# CrackberryPi_1_0_6_2_random3.net
KiCad netlist of a schematic drawn in EAGLE
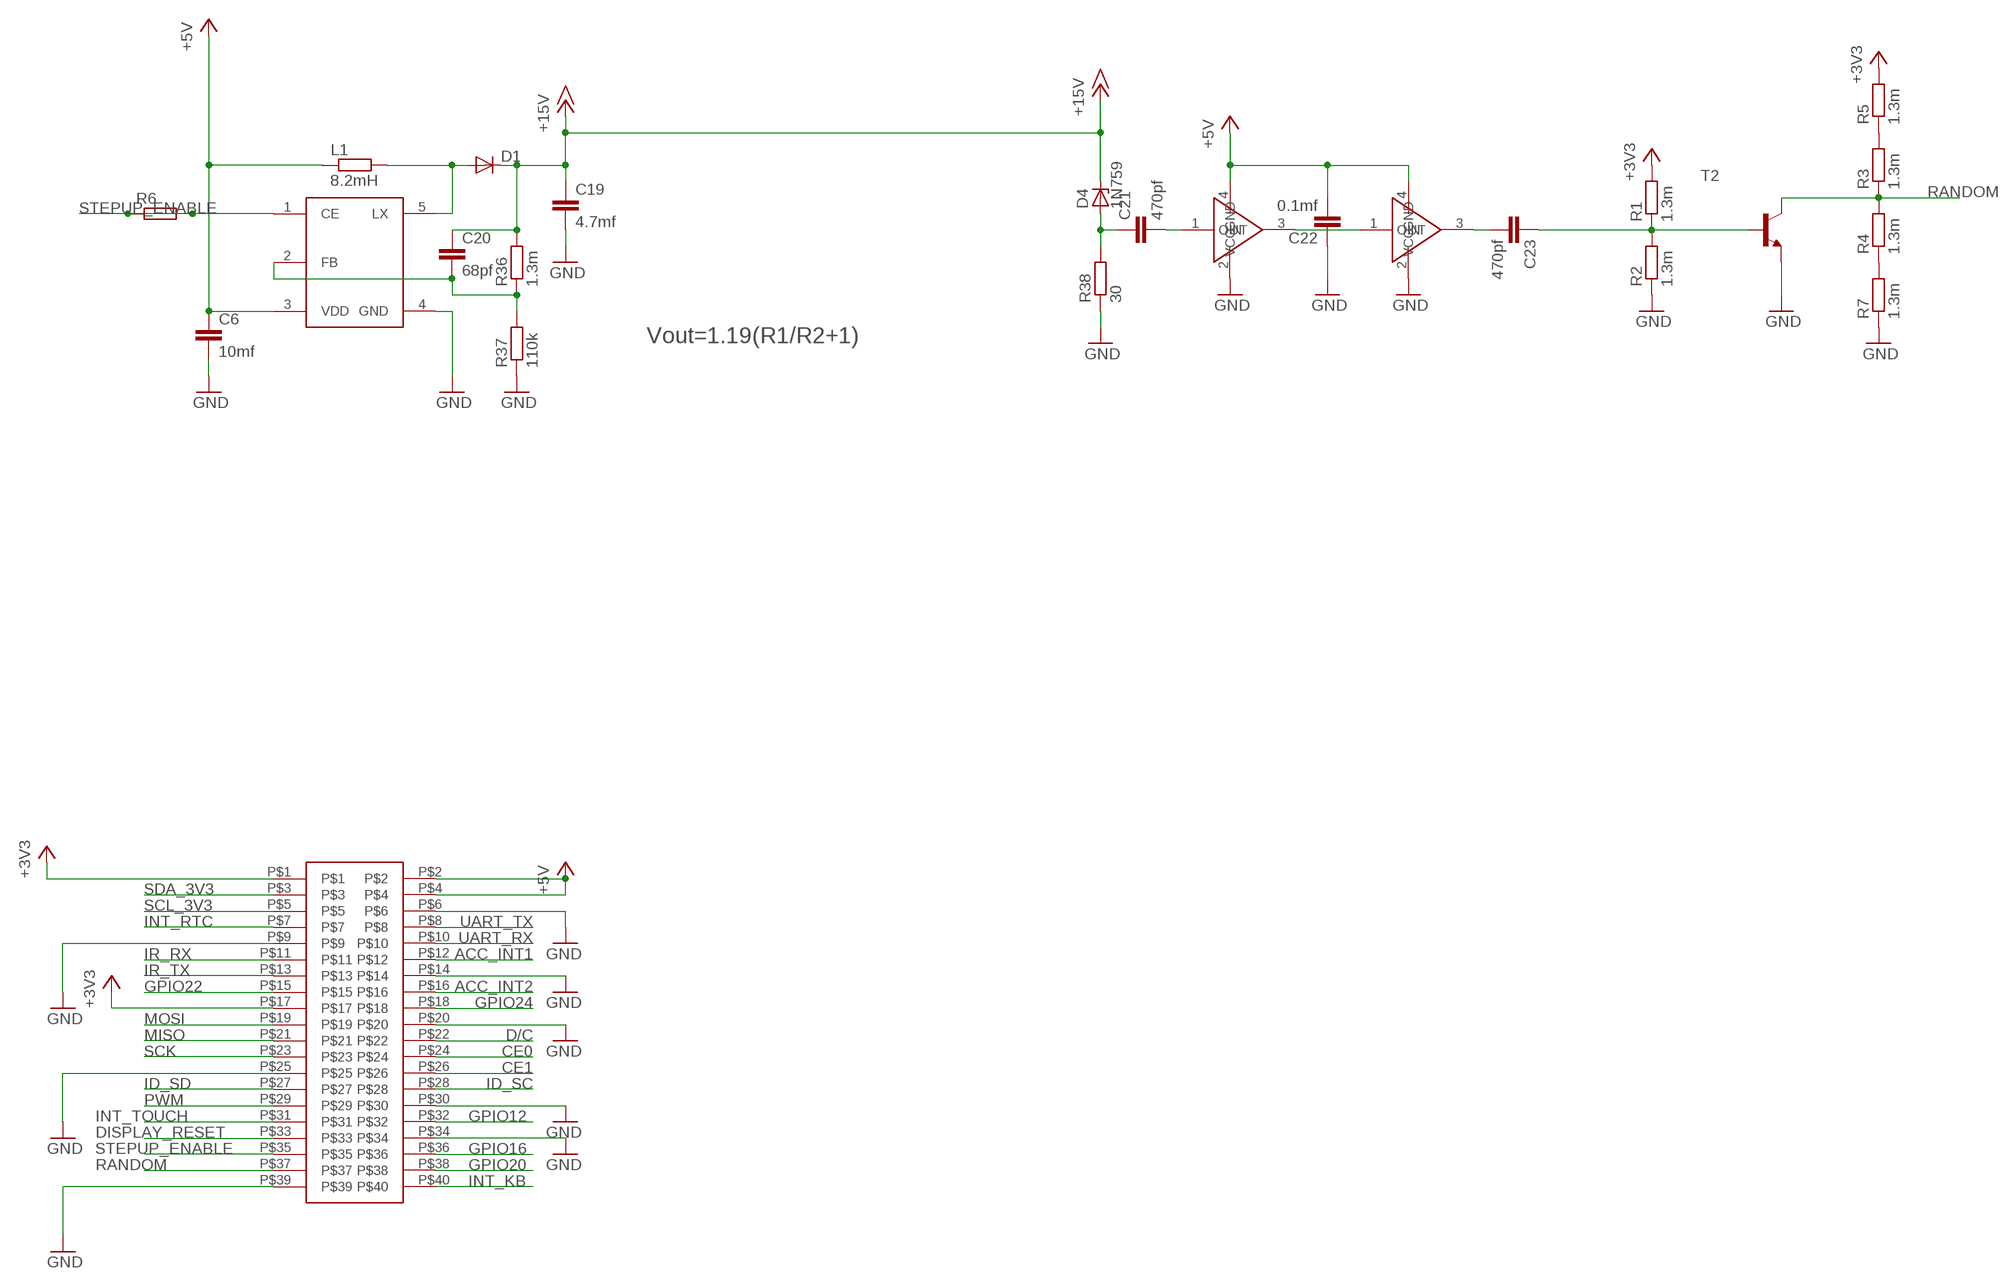
[diagram p0: schematic, sheet 1]

(export (version "E")
  (design (tool "Eeschema 10.0.6"))
  (components
    (comp (ref "C6")
      (value "10mf")
      (footprint "eagle-import:C0603")
      (libsource (lib "eagle-import") (part "C-EUC0603"))
    )
    (comp (ref "C19")
      (value "4.7mf")
      (footprint "eagle-import:C0603")
      (libsource (lib "eagle-import") (part "C-EUC0603"))
    )
    (comp (ref "C20")
      (value "68pf")
      (footprint "eagle-import:C0603")
      (libsource (lib "eagle-import") (part "C-EUC0603"))
    )
    (comp (ref "C21")
      (value "470pf")
      (footprint "eagle-import:C0603")
      (libsource (lib "eagle-import") (part "C-EUC0603"))
    )
    (comp (ref "C22")
      (value "0.1mf")
      (footprint "eagle-import:C0603")
      (libsource (lib "eagle-import") (part "C-EUC0603"))
    )
    (comp (ref "C23")
      (value "470pf")
      (footprint "eagle-import:C0603")
      (libsource (lib "eagle-import") (part "C-EUC0603"))
    )
    (comp (ref "D1")
      (value "DIODE-SOD123")
      (footprint "eagle-import:SOD123")
      (libsource (lib "eagle-import") (part "DIODE-SOD123"))
    )
    (comp (ref "D4")
      (value "1N759")
      (footprint "eagle-import:SOD80C")
      (libsource (lib "eagle-import") (part "ZENER-DIODESOD80C"))
    )
    (comp (ref "L1")
      (value "8.2mH")
      (footprint "eagle-import:R1210")
      (libsource (lib "eagle-import") (part "R-EU_R1210"))
    )
    (comp (ref "R1")
      (value "1.3m")
      (footprint "eagle-import:R0603")
      (libsource (lib "eagle-import") (part "R-EU_R0603"))
    )
    (comp (ref "R2")
      (value "1.3m")
      (footprint "eagle-import:R0603")
      (libsource (lib "eagle-import") (part "R-EU_R0603"))
    )
    (comp (ref "R3")
      (value "1.3m")
      (footprint "eagle-import:R0603")
      (libsource (lib "eagle-import") (part "R-EU_R0603"))
    )
    (comp (ref "R4")
      (value "1.3m")
      (footprint "eagle-import:R0603")
      (libsource (lib "eagle-import") (part "R-EU_R0603"))
    )
    (comp (ref "R5")
      (value "1.3m")
      (footprint "eagle-import:R0603")
      (libsource (lib "eagle-import") (part "R-EU_R0603"))
    )
    (comp (ref "R6")
      (value "R-EU_R1210")
      (footprint "eagle-import:R1210")
      (libsource (lib "eagle-import") (part "R-EU_R1210"))
    )
    (comp (ref "R7")
      (value "1.3m")
      (footprint "eagle-import:R0603")
      (libsource (lib "eagle-import") (part "R-EU_R0603"))
    )
    (comp (ref "R36")
      (value "1.3m")
      (footprint "eagle-import:R0603")
      (libsource (lib "eagle-import") (part "R-EU_R0603"))
    )
    (comp (ref "R37")
      (value "110k")
      (footprint "eagle-import:R0603")
      (libsource (lib "eagle-import") (part "R-EU_R0603"))
    )
    (comp (ref "R38")
      (value "30")
      (footprint "eagle-import:R0603")
      (libsource (lib "eagle-import") (part "R-EU_R0603"))
    )
    (comp (ref "T2")
      (value "-NPN-SOT23-EBC")
      (footprint "eagle-import:SOT23-EBC")
      (libsource (lib "eagle-import") (part "-NPN-SOT23-EBC"))
    )
    (comp (ref "U$2")
      (value "NCP1406")
      (footprint "eagle-import:SOT23-5L")
      (libsource (lib "eagle-import") (part "NCP1406"))
    )
    (comp (ref "U$3")
      (value "MAX2650")
      (footprint "eagle-import:SOT143-W")
      (libsource (lib "eagle-import") (part "MAX2650"))
    )
    (comp (ref "U$10")
      (value "MAX2650")
      (footprint "eagle-import:SOT143-W")
      (libsource (lib "eagle-import") (part "MAX2650"))
    )
    (comp (ref "U$11")
      (value "HEADER")
      (footprint "eagle-import:20X2")
      (libsource (lib "eagle-import") (part "HEADER"))
    )
  )
  (nets
    (net (code "1") (name "+3V3") (class "Default")
      (node (ref "R1") (pin "2") (pinfunction "2_2") (pintype "passive"))
      (node (ref "R5") (pin "2") (pinfunction "2_2") (pintype "passive"))
      (node (ref "U$11") (pin "P$1") (pinfunction "P$1_P$1") (pintype "bidirectional"))
      (node (ref "U$11") (pin "P$17") (pinfunction "P$17_P$17") (pintype "bidirectional"))
    )
    (net (code "2") (name "+5V") (class "Default")
      (node (ref "C22") (pin "2") (pinfunction "2_2") (pintype "passive"))
      (node (ref "C6") (pin "1") (pinfunction "1_1") (pintype "passive"))
      (node (ref "L1") (pin "1") (pinfunction "1_1") (pintype "passive"))
      (node (ref "U$10") (pin "4") (pinfunction "VCC_4") (pintype "bidirectional"))
      (node (ref "U$11") (pin "P$2") (pinfunction "P$2_P$2") (pintype "bidirectional"))
      (node (ref "U$11") (pin "P$4") (pinfunction "P$4_P$4") (pintype "bidirectional"))
      (node (ref "U$2") (pin "3") (pinfunction "VDD_3") (pintype "bidirectional"))
      (node (ref "U$3") (pin "4") (pinfunction "VCC_4") (pintype "bidirectional"))
    )
    (net (code "3") (name "+15V") (class "Default")
      (node (ref "C19") (pin "1") (pinfunction "1_1") (pintype "passive"))
      (node (ref "C20") (pin "1") (pinfunction "1_1") (pintype "passive"))
      (node (ref "D1") (pin "C") (pinfunction "C_C") (pintype "passive"))
      (node (ref "D4") (pin "C") (pinfunction "C_C") (pintype "passive"))
      (node (ref "R36") (pin "2") (pinfunction "2_2") (pintype "passive"))
    )
    (net (code "4") (name "/ACC_INT1") (class "Default")
      (node (ref "U$11") (pin "P$12") (pinfunction "P$12_P$12") (pintype "bidirectional"))
    )
    (net (code "5") (name "/ACC_INT2") (class "Default")
      (node (ref "U$11") (pin "P$16") (pinfunction "P$16_P$16") (pintype "bidirectional"))
    )
    (net (code "6") (name "/CE0") (class "Default")
      (node (ref "U$11") (pin "P$24") (pinfunction "P$24_P$24") (pintype "bidirectional"))
    )
    (net (code "7") (name "/CE1") (class "Default")
      (node (ref "U$11") (pin "P$26") (pinfunction "P$26_P$26") (pintype "bidirectional"))
    )
    (net (code "8") (name "/DISPLAY_RESET") (class "Default")
      (node (ref "U$11") (pin "P$33") (pinfunction "P$33_P$33") (pintype "bidirectional"))
    )
    (net (code "9") (name "/D{slash}C") (class "Default")
      (node (ref "U$11") (pin "P$22") (pinfunction "P$22_P$22") (pintype "bidirectional"))
    )
    (net (code "10") (name "/GPIO12") (class "Default")
      (node (ref "U$11") (pin "P$32") (pinfunction "P$32_P$32") (pintype "bidirectional"))
    )
    (net (code "11") (name "/GPIO16") (class "Default")
      (node (ref "U$11") (pin "P$36") (pinfunction "P$36_P$36") (pintype "bidirectional"))
    )
    (net (code "12") (name "/GPIO20") (class "Default")
      (node (ref "U$11") (pin "P$38") (pinfunction "P$38_P$38") (pintype "bidirectional"))
    )
    (net (code "13") (name "/GPIO22") (class "Default")
      (node (ref "U$11") (pin "P$15") (pinfunction "P$15_P$15") (pintype "bidirectional"))
    )
    (net (code "14") (name "/GPIO24") (class "Default")
      (node (ref "U$11") (pin "P$18") (pinfunction "P$18_P$18") (pintype "bidirectional"))
    )
    (net (code "15") (name "/ID_SC") (class "Default")
      (node (ref "U$11") (pin "P$28") (pinfunction "P$28_P$28") (pintype "bidirectional"))
    )
    (net (code "16") (name "/ID_SD") (class "Default")
      (node (ref "U$11") (pin "P$27") (pinfunction "P$27_P$27") (pintype "bidirectional"))
    )
    (net (code "17") (name "/INT_KB") (class "Default")
      (node (ref "U$11") (pin "P$40") (pinfunction "P$40_P$40") (pintype "bidirectional"))
    )
    (net (code "18") (name "/INT_RTC") (class "Default")
      (node (ref "U$11") (pin "P$7") (pinfunction "P$7_P$7") (pintype "bidirectional"))
    )
    (net (code "19") (name "/INT_TOUCH") (class "Default")
      (node (ref "U$11") (pin "P$31") (pinfunction "P$31_P$31") (pintype "bidirectional"))
    )
    (net (code "20") (name "/IR_RX") (class "Default")
      (node (ref "U$11") (pin "P$11") (pinfunction "P$11_P$11") (pintype "bidirectional"))
    )
    (net (code "21") (name "/IR_TX") (class "Default")
      (node (ref "U$11") (pin "P$13") (pinfunction "P$13_P$13") (pintype "bidirectional"))
    )
    (net (code "22") (name "/MISO") (class "Default")
      (node (ref "U$11") (pin "P$21") (pinfunction "P$21_P$21") (pintype "bidirectional"))
    )
    (net (code "23") (name "/MOSI") (class "Default")
      (node (ref "U$11") (pin "P$19") (pinfunction "P$19_P$19") (pintype "bidirectional"))
    )
    (net (code "24") (name "/PWM") (class "Default")
      (node (ref "U$11") (pin "P$29") (pinfunction "P$29_P$29") (pintype "bidirectional"))
    )
    (net (code "25") (name "/RANDOM") (class "Default")
      (node (ref "R3") (pin "1") (pinfunction "1_1") (pintype "passive"))
      (node (ref "R4") (pin "2") (pinfunction "2_2") (pintype "passive"))
      (node (ref "T2") (pin "C") (pinfunction "C_C") (pintype "passive"))
      (node (ref "U$11") (pin "P$37") (pinfunction "P$37_P$37") (pintype "bidirectional"))
    )
    (net (code "26") (name "/SCK") (class "Default")
      (node (ref "U$11") (pin "P$23") (pinfunction "P$23_P$23") (pintype "bidirectional"))
    )
    (net (code "27") (name "/SCL_3V3") (class "Default")
      (node (ref "U$11") (pin "P$5") (pinfunction "P$5_P$5") (pintype "bidirectional"))
    )
    (net (code "28") (name "/SDA_3V3") (class "Default")
      (node (ref "U$11") (pin "P$3") (pinfunction "P$3_P$3") (pintype "bidirectional"))
    )
    (net (code "29") (name "/STEPUP_ENABLE") (class "Default")
      (node (ref "R6") (pin "1") (pinfunction "1_1") (pintype "passive"))
      (node (ref "R6") (pin "2") (pinfunction "2_2") (pintype "passive"))
      (node (ref "U$11") (pin "P$35") (pinfunction "P$35_P$35") (pintype "bidirectional"))
      (node (ref "U$2") (pin "1") (pinfunction "CE_1") (pintype "bidirectional"))
    )
    (net (code "30") (name "/UART_RX") (class "Default")
      (node (ref "U$11") (pin "P$10") (pinfunction "P$10_P$10") (pintype "bidirectional"))
    )
    (net (code "31") (name "/UART_TX") (class "Default")
      (node (ref "U$11") (pin "P$8") (pinfunction "P$8_P$8") (pintype "bidirectional"))
    )
    (net (code "32") (name "GND") (class "Default")
      (node (ref "C19") (pin "2") (pinfunction "2_2") (pintype "passive"))
      (node (ref "C22") (pin "1") (pinfunction "1_1") (pintype "passive"))
      (node (ref "C6") (pin "2") (pinfunction "2_2") (pintype "passive"))
      (node (ref "R2") (pin "1") (pinfunction "1_1") (pintype "passive"))
      (node (ref "R37") (pin "1") (pinfunction "1_1") (pintype "passive"))
      (node (ref "R38") (pin "1") (pinfunction "1_1") (pintype "passive"))
      (node (ref "R7") (pin "1") (pinfunction "1_1") (pintype "passive"))
      (node (ref "T2") (pin "E") (pinfunction "E_E") (pintype "passive"))
      (node (ref "U$10") (pin "2") (pinfunction "GND_2") (pintype "bidirectional"))
      (node (ref "U$11") (pin "P$14") (pinfunction "P$14_P$14") (pintype "bidirectional"))
      (node (ref "U$11") (pin "P$20") (pinfunction "P$20_P$20") (pintype "bidirectional"))
      (node (ref "U$11") (pin "P$25") (pinfunction "P$25_P$25") (pintype "bidirectional"))
      (node (ref "U$11") (pin "P$30") (pinfunction "P$30_P$30") (pintype "bidirectional"))
      (node (ref "U$11") (pin "P$34") (pinfunction "P$34_P$34") (pintype "bidirectional"))
      (node (ref "U$11") (pin "P$39") (pinfunction "P$39_P$39") (pintype "bidirectional"))
      (node (ref "U$11") (pin "P$6") (pinfunction "P$6_P$6") (pintype "bidirectional"))
      (node (ref "U$11") (pin "P$9") (pinfunction "P$9_P$9") (pintype "bidirectional"))
      (node (ref "U$2") (pin "4") (pinfunction "GND_4") (pintype "bidirectional"))
      (node (ref "U$3") (pin "2") (pinfunction "GND_2") (pintype "bidirectional"))
    )
    (net (code "33") (name "Net-(C21-Pad1)") (class "Default")
      (node (ref "C21") (pin "1") (pinfunction "1_1") (pintype "passive"))
      (node (ref "D4") (pin "A") (pinfunction "A_A") (pintype "passive"))
      (node (ref "R38") (pin "2") (pinfunction "2_2") (pintype "passive"))
    )
    (net (code "34") (name "Net-(C23-Pad1)") (class "Default")
      (node (ref "C23") (pin "1") (pinfunction "1_1") (pintype "passive"))
      (node (ref "R1") (pin "1") (pinfunction "1_1") (pintype "passive"))
      (node (ref "R2") (pin "2") (pinfunction "2_2") (pintype "passive"))
      (node (ref "T2") (pin "B") (pinfunction "B_B") (pintype "passive"))
    )
    (net (code "35") (name "Net-(R3-Pad2)") (class "Default")
      (node (ref "R3") (pin "2") (pinfunction "2_2") (pintype "passive"))
      (node (ref "R5") (pin "1") (pinfunction "1_1") (pintype "passive"))
    )
    (net (code "36") (name "Net-(R4-Pad1)") (class "Default")
      (node (ref "R4") (pin "1") (pinfunction "1_1") (pintype "passive"))
      (node (ref "R7") (pin "2") (pinfunction "2_2") (pintype "passive"))
    )
    (net (code "37") (name "Net-(U$2-FB)") (class "Default")
      (node (ref "C20") (pin "2") (pinfunction "2_2") (pintype "passive"))
      (node (ref "R36") (pin "1") (pinfunction "1_1") (pintype "passive"))
      (node (ref "R37") (pin "2") (pinfunction "2_2") (pintype "passive"))
      (node (ref "U$2") (pin "2") (pinfunction "FB_2") (pintype "bidirectional"))
    )
    (net (code "38") (name "Net-(U$2-LX)") (class "Default")
      (node (ref "D1") (pin "A") (pinfunction "A_A") (pintype "passive"))
      (node (ref "L1") (pin "2") (pinfunction "2_2") (pintype "passive"))
      (node (ref "U$2") (pin "5") (pinfunction "LX_5") (pintype "bidirectional"))
    )
    (net (code "39") (name "Net-(U$3-IN)") (class "Default")
      (node (ref "C21") (pin "2") (pinfunction "2_2") (pintype "passive"))
      (node (ref "U$3") (pin "1") (pinfunction "IN_1") (pintype "bidirectional"))
    )
    (net (code "40") (name "Net-(U$10-IN)") (class "Default")
      (node (ref "U$10") (pin "1") (pinfunction "IN_1") (pintype "bidirectional"))
      (node (ref "U$3") (pin "3") (pinfunction "OUT_3") (pintype "bidirectional"))
    )
    (net (code "41") (name "Net-(U$10-OUT)") (class "Default")
      (node (ref "C23") (pin "2") (pinfunction "2_2") (pintype "passive"))
      (node (ref "U$10") (pin "3") (pinfunction "OUT_3") (pintype "bidirectional"))
    )
  )
)
